# kernel_RJ45.net
KiCad netlist of a schematic drawn in Altium Designer
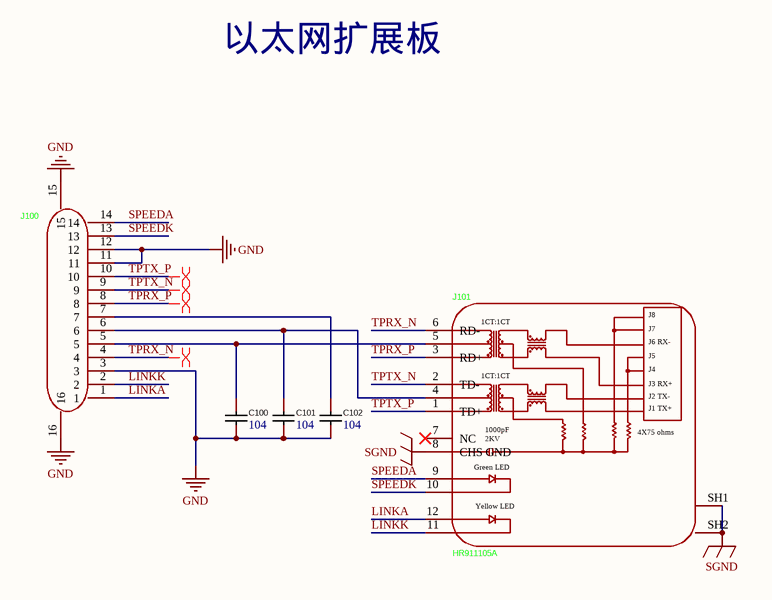
[diagram p0: kernel_RJ45.SchDoc]

(export (version "E")
  (design (tool "Eeschema 10.0.6"))
  (components
    (comp (ref "C100")
      (value "104")
      (footprint "0402_C")
      (description "电容100nf")
      (fields (field (name "MANUFACTURER") "FH(风华)") (field (name "MANUFACTURER PART") "0402CG200J500NT"))
      (libsource (lib "altium-import") (part "root_1_0402C_104_"))
    )
    (comp (ref "C101")
      (value "104")
      (footprint "0402_C")
      (description "电容100nf")
      (fields (field (name "MANUFACTURER") "FH(风华)") (field (name "MANUFACTURER PART") "0402CG200J500NT"))
      (libsource (lib "altium-import") (part "root_1_0402C_104_"))
    )
    (comp (ref "C102")
      (value "104")
      (footprint "0402_C")
      (description "电容100nf")
      (fields (field (name "MANUFACTURER") "FH(风华)") (field (name "MANUFACTURER PART") "0402CG200J500NT"))
      (libsource (lib "altium-import") (part "root_1_0402C_104_"))
    )
    (comp (ref "J100")
      (value "AFC01-S14FCA-00")
      (footprint "FPC-SMD_AFC01-S14FCA-00")
      (description "FPC")
      (fields (field (name "MANUFACTURER") "JS(钜硕电子)"))
      (libsource (lib "altium-import") (part "root_2_AFC01-S14FCA-00_"))
    )
    (comp (ref "J101")
      (value "HR911105A")
      (footprint "RJ45-TH_HR911105A")
      (fields (field (name "MANUFACTURER") "HANRUN(汉仁)"))
      (libsource (lib "altium-import") (part "root_0_HR911105A_C12074_"))
    )
  )
  (nets
    (net (code "1") (name "/LINKA") (class "Default")
      (node (ref "J100") (pin "1") (pinfunction "1_1") (pintype "passive"))
      (node (ref "J101") (pin "12") (pinfunction "12_12") (pintype "passive"))
    )
    (net (code "2") (name "/LINKK") (class "Default")
      (node (ref "J100") (pin "2") (pinfunction "2_2") (pintype "passive"))
      (node (ref "J101") (pin "11") (pinfunction "11_11") (pintype "passive"))
    )
    (net (code "3") (name "/SPEEDA") (class "Default")
      (node (ref "J100") (pin "14") (pinfunction "14_14") (pintype "passive"))
      (node (ref "J101") (pin "9") (pinfunction "9_9") (pintype "passive"))
    )
    (net (code "4") (name "/SPEEDK") (class "Default")
      (node (ref "J100") (pin "13") (pinfunction "13_13") (pintype "passive"))
      (node (ref "J101") (pin "10") (pinfunction "10_10") (pintype "passive"))
    )
    (net (code "5") (name "/TPRX_N") (class "Default")
      (node (ref "J100") (pin "4") (pinfunction "4_4") (pintype "passive"))
      (node (ref "J101") (pin "6") (pinfunction "RD-_6") (pintype "passive"))
    )
    (net (code "6") (name "/TPRX_P") (class "Default")
      (node (ref "J100") (pin "8") (pinfunction "8_8") (pintype "passive"))
      (node (ref "J101") (pin "3") (pinfunction "RD+_3") (pintype "passive"))
    )
    (net (code "7") (name "/TPTX_N") (class "Default")
      (node (ref "J100") (pin "9") (pinfunction "9_9") (pintype "passive"))
      (node (ref "J101") (pin "2") (pinfunction "TD-_2") (pintype "passive"))
    )
    (net (code "8") (name "/TPTX_P") (class "Default")
      (node (ref "J100") (pin "10") (pinfunction "10_10") (pintype "passive"))
      (node (ref "J101") (pin "1") (pinfunction "TD+_1") (pintype "passive"))
    )
    (net (code "9") (name "GND") (class "Default")
      (node (ref "C100") (pin "1") (pinfunction "1_1") (pintype "passive"))
      (node (ref "C101") (pin "1") (pinfunction "1_1") (pintype "passive"))
      (node (ref "C102") (pin "1") (pinfunction "1_1") (pintype "passive"))
      (node (ref "J100") (pin "11") (pinfunction "11_11") (pintype "passive"))
      (node (ref "J100") (pin "12") (pinfunction "12_12") (pintype "passive"))
      (node (ref "J100") (pin "15") (pinfunction "15_15") (pintype "passive"))
      (node (ref "J100") (pin "16") (pinfunction "16_16") (pintype "passive"))
      (node (ref "J100") (pin "3") (pinfunction "3_3") (pintype "passive"))
    )
    (net (code "10") (name "Net-(C100-Pad2)") (class "Default")
      (node (ref "C100") (pin "2") (pinfunction "2_2") (pintype "passive"))
      (node (ref "J100") (pin "5") (pinfunction "5_5") (pintype "passive"))
      (node (ref "J101") (pin "5") (pinfunction "5_5") (pintype "passive"))
    )
    (net (code "11") (name "Net-(C101-Pad2)") (class "Default")
      (node (ref "C101") (pin "2") (pinfunction "2_2") (pintype "passive"))
      (node (ref "J100") (pin "6") (pinfunction "6_6") (pintype "passive"))
      (node (ref "J101") (pin "4") (pinfunction "4_4") (pintype "passive"))
    )
    (net (code "12") (name "Net-(C102-Pad2)") (class "Default")
      (node (ref "C102") (pin "2") (pinfunction "2_2") (pintype "passive"))
      (node (ref "J100") (pin "7") (pinfunction "7_7") (pintype "passive"))
    )
    (net (code "13") (name "SGND") (class "Default")
      (node (ref "J101") (pin "8") (pinfunction "CHS_GND_8") (pintype "passive"))
      (node (ref "J101") (pin "SH1") (pinfunction "SH1_SH1") (pintype "passive"))
      (node (ref "J101") (pin "SH2") (pinfunction "SH2_SH2") (pintype "passive"))
    )
    (net (code "14") (name "unconnected-(J101-NC-Pad7)") (class "Default")
      (node (ref "J101") (pin "7") (pinfunction "NC_7") (pintype "passive+no_connect"))
    )
  )
)
